# apb.net
KiCad netlist of a schematic drawn in Altium Designer
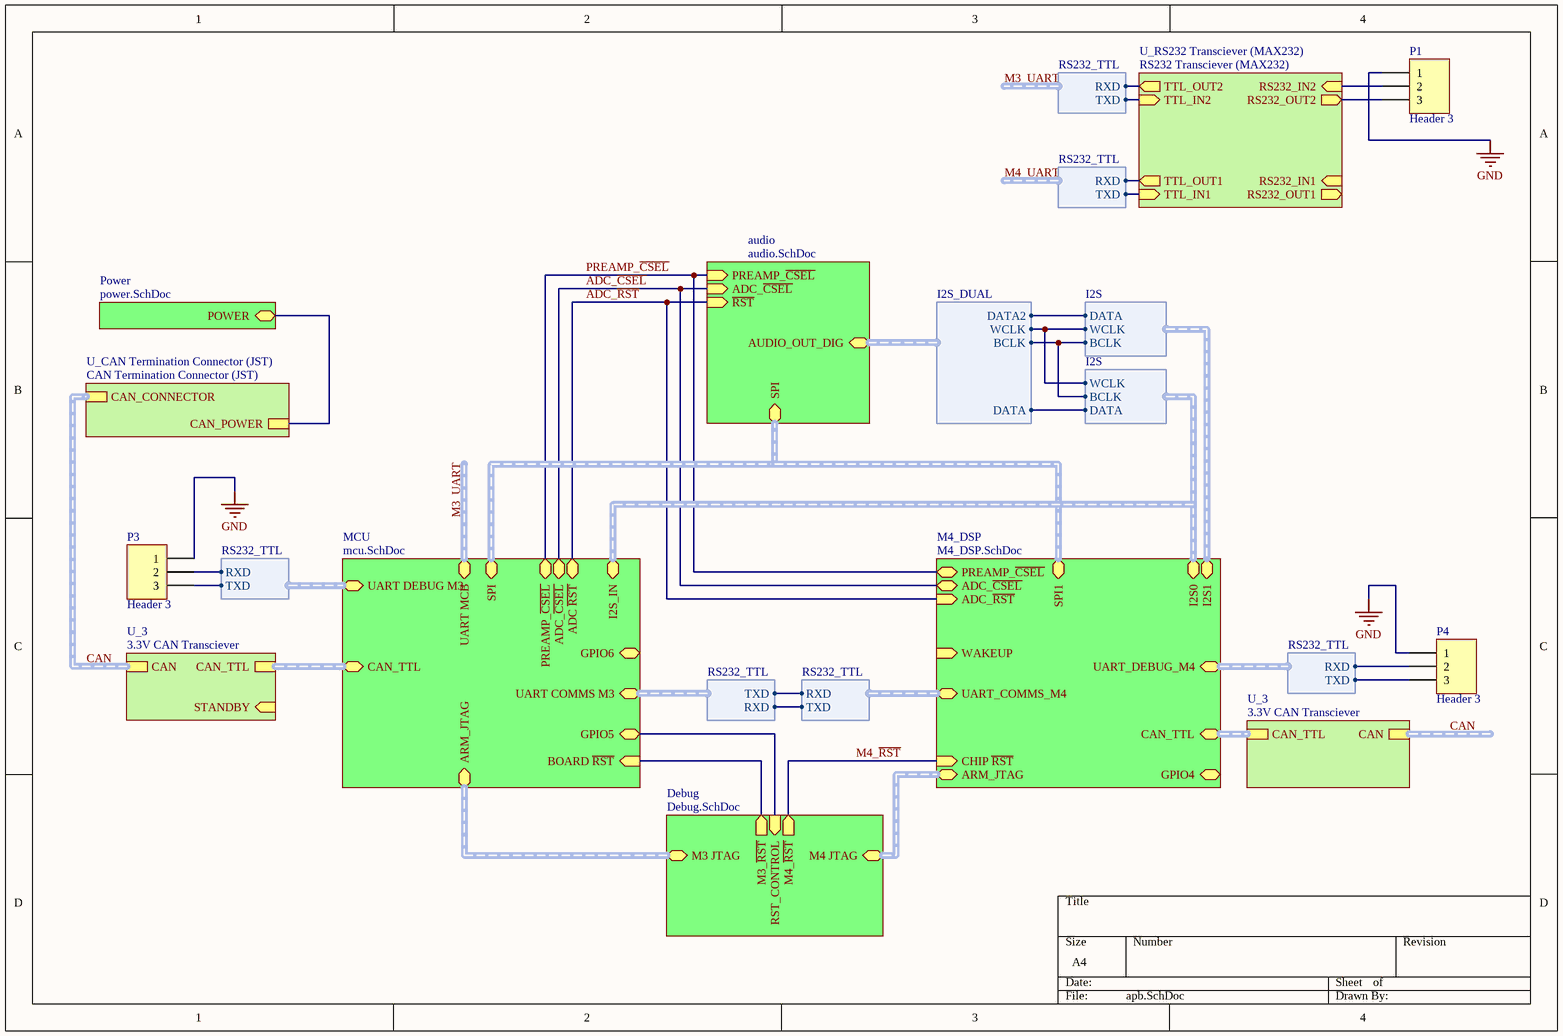
[diagram p0: apb.SchDoc]

(export (version "E")
  (design (tool "Eeschema 10.0.6"))
  (components
    (comp (ref "P1")
      (value "Header 3")
      (footprint "S03B-PASK-2")
      (description "Header, 3-Pin")
      (fields (field (name "PUBLISHER") "Altium Limited"))
      (libsource (lib "") (part "Header 3_1"))
    )
    (comp (ref "P3")
      (value "Header 3")
      (footprint "HDR1X3")
      (description "Header, 3-Pin")
      (fields (field (name "PUBLISHER") "Altium Limited"))
      (libsource (lib "Miscellaneous Connectors") (part "Header 3"))
    )
    (comp (ref "P4")
      (value "Header 3")
      (footprint "HDR1X3")
      (description "Header, 3-Pin")
      (fields (field (name "PUBLISHER") "Altium Limited"))
      (libsource (lib "") (part "Header 3_1"))
    )
  )
  (nets
    (net (code "25") (name "/RS232_IN2") (class "Default")
      (node (ref "P1") (pin "2") (pinfunction "2_2") (pintype "passive"))
    )
    (net (code "27") (name "/RS232_OUT2") (class "Default")
      (node (ref "P1") (pin "3") (pinfunction "3_3") (pintype "passive"))
    )
    (net (code "40") (name "GND") (class "Default")
      (node (ref "P1") (pin "1") (pinfunction "1_1") (pintype "passive"))
      (node (ref "P3") (pin "1") (pinfunction "1_1") (pintype "passive"))
      (node (ref "P4") (pin "1") (pinfunction "1_1") (pintype "passive"))
    )
    (net (code "41") (name "unconnected-(P3-Pad2)") (class "Default")
      (node (ref "P3") (pin "2") (pinfunction "2_2") (pintype "passive"))
    )
    (net (code "42") (name "unconnected-(P3-Pad3)") (class "Default")
      (node (ref "P3") (pin "3") (pinfunction "3_3") (pintype "passive"))
    )
    (net (code "43") (name "unconnected-(P4-Pad2)") (class "Default")
      (node (ref "P4") (pin "2") (pinfunction "2_2") (pintype "passive"))
    )
    (net (code "44") (name "unconnected-(P4-Pad3)") (class "Default")
      (node (ref "P4") (pin "3") (pinfunction "3_3") (pintype "passive"))
    )
  )
)
